# FootSW.net
KiCad netlist of a schematic drawn in Altium Designer
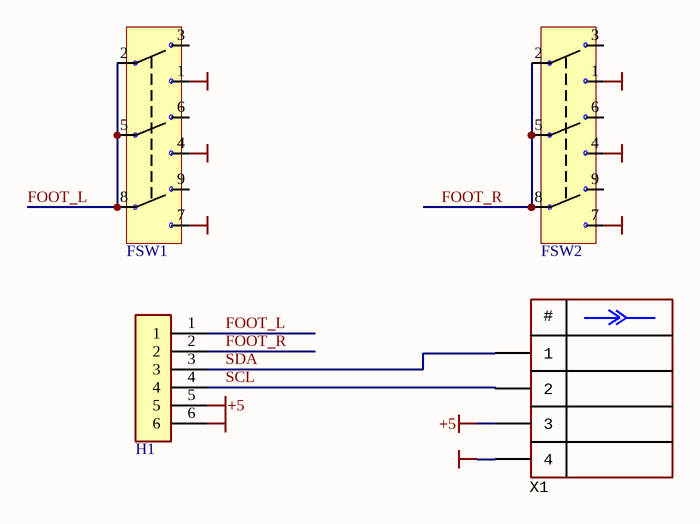
[diagram p0: FootSW.SchDoc]

(export (version "E")
  (design (tool "Eeschema 10.0.6"))
  (components
    (comp (ref "FSW1")
      (value "FootSwitch")
      (footprint "ProtoStack_H750VBT:FOOTSW")
      (libsource (lib "ProtoStack_H750VBT") (part "FootSwitch"))
    )
    (comp (ref "FSW2")
      (value "FootSwitch")
      (footprint "ProtoStack_H750VBT:FOOTSW")
      (libsource (lib "ProtoStack_H750VBT") (part "FootSwitch"))
    )
    (comp (ref "H1")
      (value "1.5-6A")
      (footprint "ProtoStack_H750VBT:1.5-6A")
      (description "Pin Header p=1.5mm, 6 pins")
      (libsource (lib "ProtoStack_H750VBT") (part "1.5-6A"))
    )
    (comp (ref "X1")
      (value "~")
      (footprint "CON: PBS-4")
      (fields
        (field (name "MANUFACTURER") "Connfly")
        (field (name "VALUEMANUFACTURERPARTNUMBER") "Connector, 4pin, 2.54mm, 500VAC, 3A")
        (field (name "PARTNUMBER") "PBS-4")
      )
      (libsource (lib "connector") (part "PBS-4"))
    )
  )
  (nets
    (net (code "1") (name "+5") (class "Default")
      (node (ref "H1") (pin "5") (pinfunction "5_5") (pintype "passive"))
      (node (ref "X1") (pin "3") (pinfunction "3_3") (pintype "power_in"))
    )
    (net (code "2") (name "/FOOT_L") (class "Default")
      (node (ref "FSW1") (pin "2") (pinfunction "2_2") (pintype "passive"))
      (node (ref "FSW1") (pin "5") (pinfunction "5_5") (pintype "passive"))
      (node (ref "FSW1") (pin "8") (pinfunction "8_8") (pintype "passive"))
      (node (ref "H1") (pin "1") (pinfunction "1_1") (pintype "passive"))
    )
    (net (code "3") (name "/FOOT_R") (class "Default")
      (node (ref "FSW2") (pin "2") (pinfunction "2_2") (pintype "passive"))
      (node (ref "FSW2") (pin "5") (pinfunction "5_5") (pintype "passive"))
      (node (ref "FSW2") (pin "8") (pinfunction "8_8") (pintype "passive"))
      (node (ref "H1") (pin "2") (pinfunction "2_2") (pintype "passive"))
    )
    (net (code "4") (name "/SC~{L}") (class "Default")
      (node (ref "H1") (pin "4") (pinfunction "4_4") (pintype "passive"))
      (node (ref "X1") (pin "2") (pinfunction "2_2") (pintype "passive"))
    )
    (net (code "5") (name "/SDA") (class "Default")
      (node (ref "H1") (pin "3") (pinfunction "3_3") (pintype "passive"))
      (node (ref "X1") (pin "1") (pinfunction "1_1") (pintype "passive"))
    )
    (net (code "6") (name "GND") (class "Default")
      (node (ref "FSW1") (pin "1") (pinfunction "1_1") (pintype "passive"))
      (node (ref "FSW1") (pin "4") (pinfunction "4_4") (pintype "passive"))
      (node (ref "FSW1") (pin "7") (pinfunction "7_7") (pintype "passive"))
      (node (ref "FSW2") (pin "1") (pinfunction "1_1") (pintype "passive"))
      (node (ref "FSW2") (pin "4") (pinfunction "4_4") (pintype "passive"))
      (node (ref "FSW2") (pin "7") (pinfunction "7_7") (pintype "passive"))
      (node (ref "H1") (pin "6") (pinfunction "6_6") (pintype "passive"))
      (node (ref "X1") (pin "4") (pinfunction "4_4") (pintype "power_in"))
    )
    (net (code "7") (name "unconnected-(FSW1-Pad3)") (class "Default")
      (node (ref "FSW1") (pin "3") (pinfunction "3_3") (pintype "passive"))
    )
    (net (code "8") (name "unconnected-(FSW1-Pad6)") (class "Default")
      (node (ref "FSW1") (pin "6") (pinfunction "6_6") (pintype "passive"))
    )
    (net (code "9") (name "unconnected-(FSW1-Pad9)") (class "Default")
      (node (ref "FSW1") (pin "9") (pinfunction "9_9") (pintype "passive"))
    )
    (net (code "10") (name "unconnected-(FSW2-Pad3)") (class "Default")
      (node (ref "FSW2") (pin "3") (pinfunction "3_3") (pintype "passive"))
    )
    (net (code "11") (name "unconnected-(FSW2-Pad6)") (class "Default")
      (node (ref "FSW2") (pin "6") (pinfunction "6_6") (pintype "passive"))
    )
    (net (code "12") (name "unconnected-(FSW2-Pad9)") (class "Default")
      (node (ref "FSW2") (pin "9") (pinfunction "9_9") (pintype "passive"))
    )
  )
)
